# PDM-S01-V00-Microcontroller.net
KiCad netlist of a schematic drawn in Altium Designer
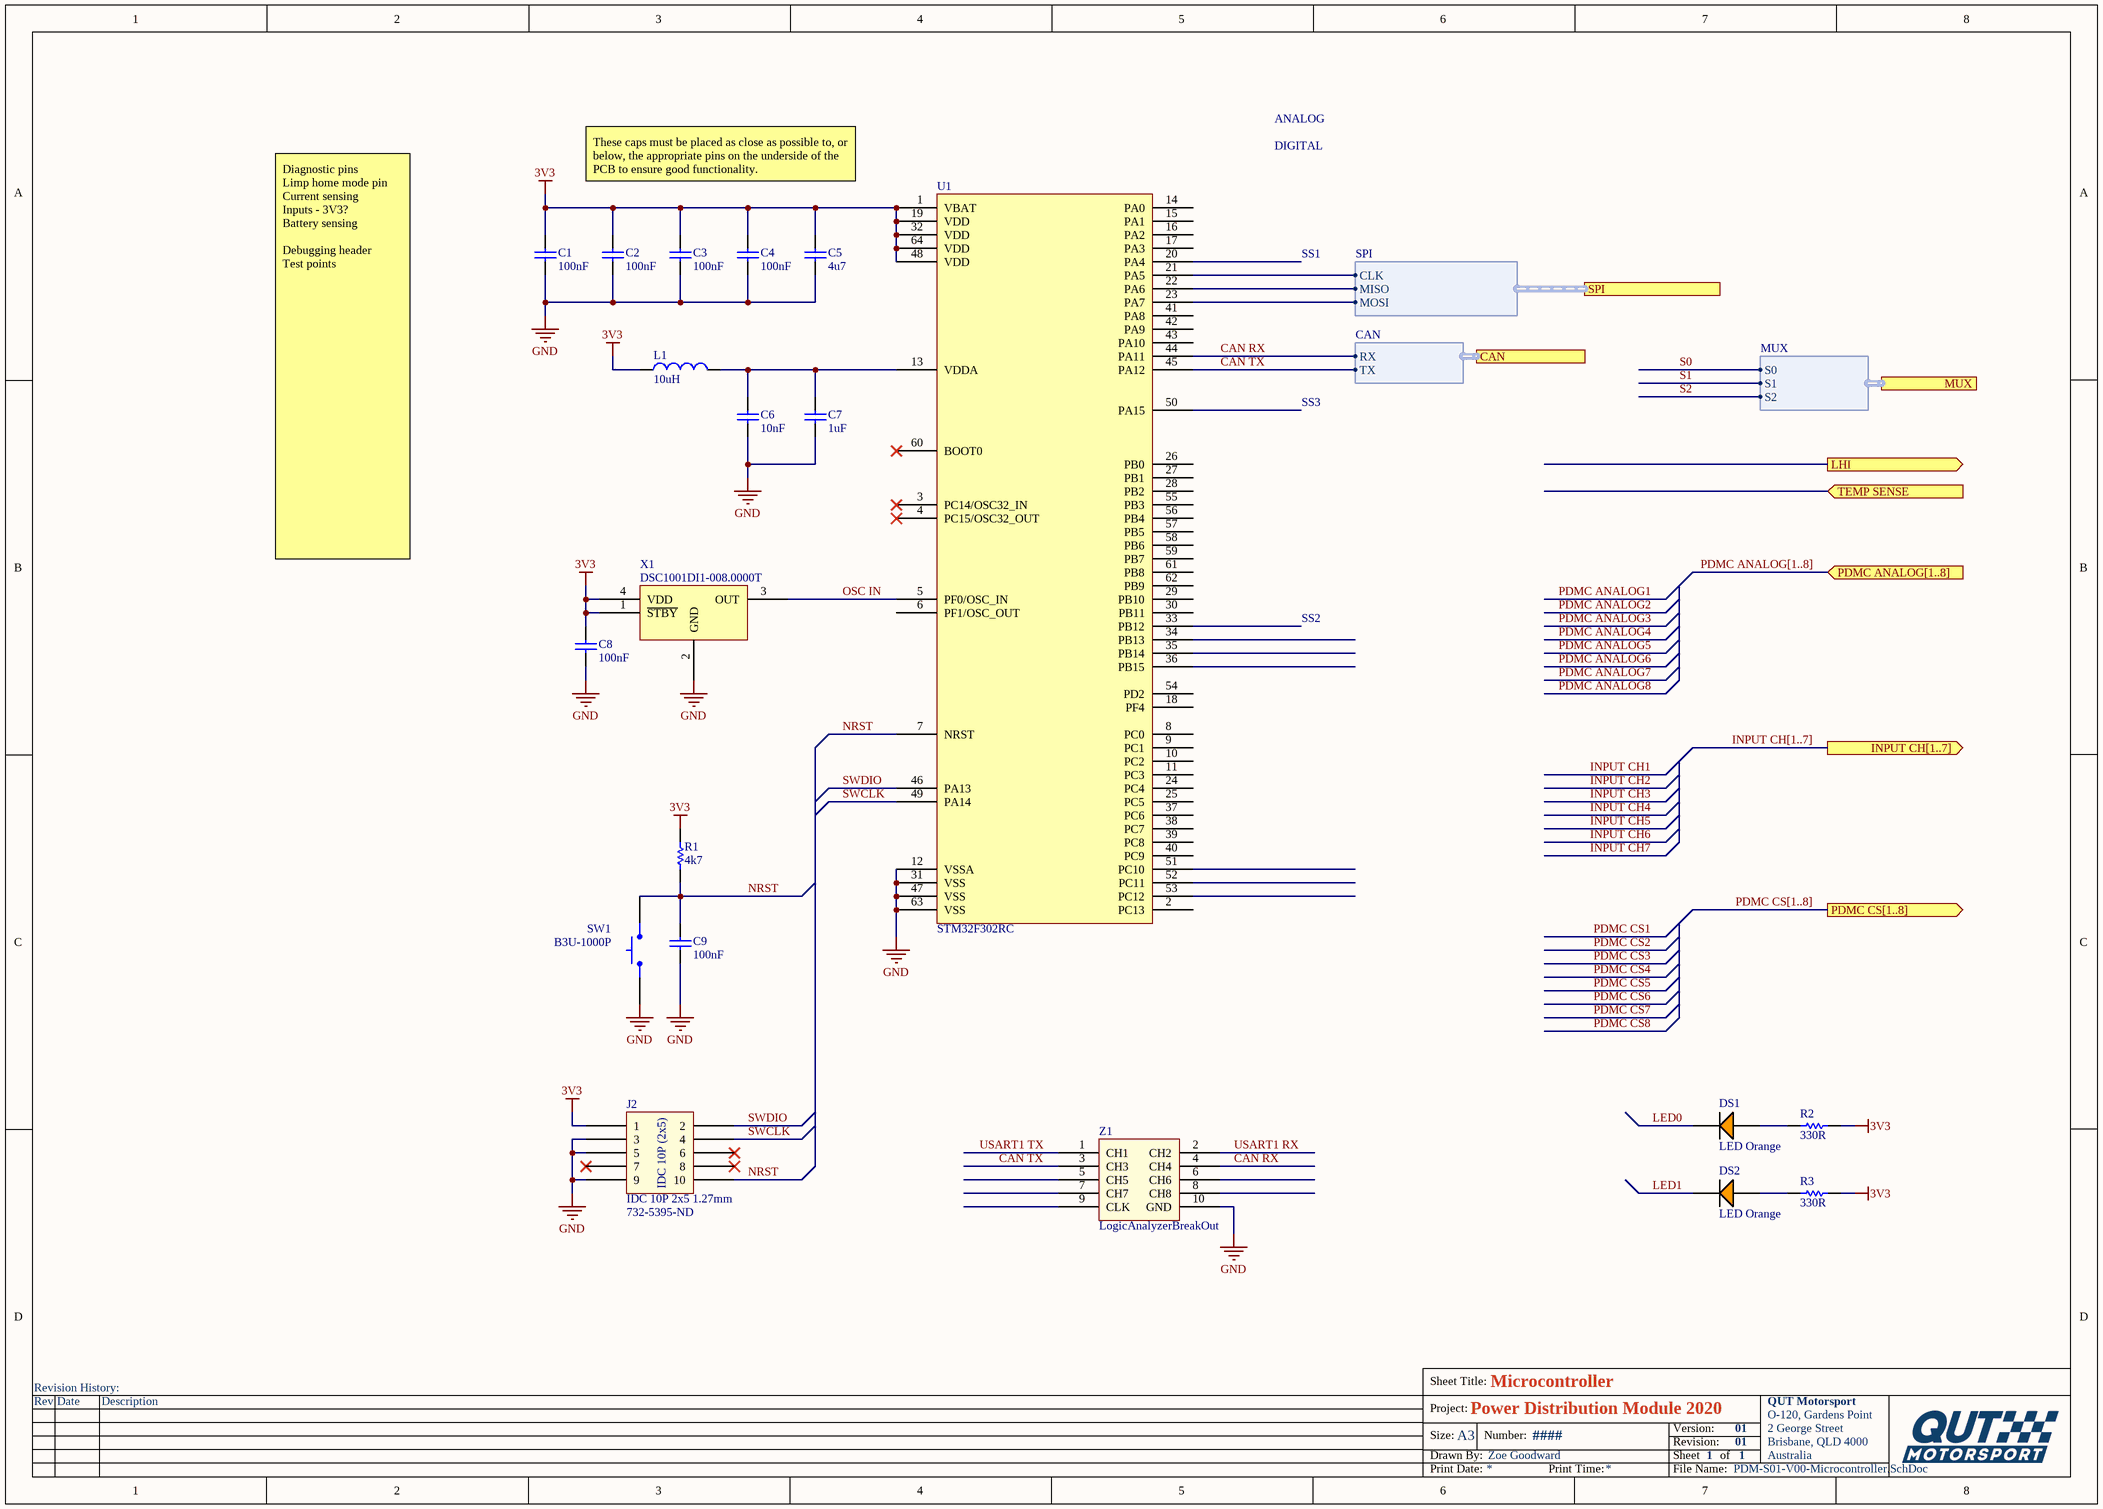
[diagram p0: PDM-S01-V00-Microcontroller.SchDoc]

(export (version "E")
  (design (tool "Eeschema 10.0.6"))
  (components
    (comp (ref "C1")
      (value "100nF")
      (footprint "Cap_Ceramic_0603")
      (description "Capacitor, Ceramic, SMD, 100nF, 50V, 5%, X7R, 0603")
      (libsource (lib "StandardCapacitors") (part "100nF 50V 5% X7R 0603"))
    )
    (comp (ref "C2")
      (value "100nF")
      (footprint "Cap_Ceramic_0603")
      (description "Capacitor, Ceramic, SMD, 100nF, 50V, 5%, X7R, 0603")
      (libsource (lib "StandardCapacitors") (part "100nF 50V 5% X7R 0603"))
    )
    (comp (ref "C3")
      (value "100nF")
      (footprint "Cap_Ceramic_0603")
      (description "Capacitor, Ceramic, SMD, 100nF, 50V, 5%, X7R, 0603")
      (libsource (lib "StandardCapacitors") (part "100nF 50V 5% X7R 0603"))
    )
    (comp (ref "C4")
      (value "100nF")
      (footprint "Cap_Ceramic_0603")
      (description "Capacitor, Ceramic, SMD, 100nF, 50V, 5%, X7R, 0603")
      (libsource (lib "StandardCapacitors") (part "100nF 50V 5% X7R 0603"))
    )
    (comp (ref "C5")
      (value "4u7")
      (footprint "Cap_Ceramic_0603")
      (description "Capacitor, Ceramic, SMD, 4u7, 50V, 5%, X7R, 0603")
      (libsource (lib "StandardCapacitors") (part "4u7 50V 5% X7R 0603"))
    )
    (comp (ref "C6")
      (value "10nF")
      (footprint "Cap_Ceramic_0603")
      (description "Capacitor, Ceramic, SMD, 10nF, 50V, 5%, X7R, 0603")
      (libsource (lib "StandardCapacitors") (part "10nF 50V 5% X7R 0603"))
    )
    (comp (ref "C7")
      (value "1uF")
      (footprint "Cap_Ceramic_0603")
      (description "Capacitor, Ceramic, SMD, 1uF, 25V, 5%, X7R, 0603")
      (libsource (lib "StandardCapacitors") (part "1uF 25V 5% X7R 0603"))
    )
    (comp (ref "C8")
      (value "100nF")
      (footprint "Cap_Ceramic_0603")
      (description "Capacitor, Ceramic, SMD, 100nF, 50V, 5%, X7R, 0603")
      (libsource (lib "StandardCapacitors") (part "100nF 50V 5% X7R 0603"))
    )
    (comp (ref "C9")
      (value "100nF")
      (footprint "Cap_Ceramic_0603")
      (description "Capacitor, Ceramic, SMD, 100nF, 50V, 5%, X7R, 0603")
      (libsource (lib "StandardCapacitors") (part "100nF 50V 5% X7R 0603"))
    )
    (comp (ref "DS1")
      (value "LED Orange")
      (footprint "LED ORANGE 0603")
      (libsource (lib "QUTMS_LEDLibrary") (part "LED ORANGE 0603"))
    )
    (comp (ref "DS2")
      (value "LED Orange")
      (footprint "LED ORANGE 0603")
      (libsource (lib "QUTMS_LEDLibrary") (part "LED ORANGE 0603"))
    )
    (comp (ref "J2")
      (value "IDC 10P 2x5 1.27mm")
      (footprint "IDC 1.27MM 10P")
      (libsource (lib "IDCConnectors") (part "IDC 10P 2x5 1.27mm"))
    )
    (comp (ref "L1")
      (value "10uH")
      (footprint "TDK-B82422A1103K100_V")
      (description "Wirewound Inductor, 10 uF, +/- 10%, 180 mA, -55 to 125 degC, 2-Pin SMD, RoHS, Tape and Reel")
      (fields (field (name "TOLERANCE") "±10%") (field (name "MANUFACTURER") "EPCOS-(TDK)"))
      (libsource (lib "Altium Content Vault") (part "IND-2"))
    )
    (comp (ref "R1")
      (value "4k7")
      (footprint "Res_ThinFilm_0603")
      (description "Resistor, SMD, 4k7, 0.1W, 5%, 0603")
      (libsource (lib "StandardResistors") (part "4k7 5% 0603"))
    )
    (comp (ref "R2")
      (value "330R")
      (footprint "Res_ThinFilm_0603")
      (description "Resistor, SMD, 330R, 0.1W, 5%, 0603")
      (libsource (lib "StandardResistors") (part "330R 5% 0603"))
    )
    (comp (ref "R3")
      (value "330R")
      (footprint "Res_ThinFilm_0603")
      (description "Resistor, SMD, 330R, 0.1W, 5%, 0603")
      (libsource (lib "StandardResistors") (part "330R 5% 0603"))
    )
    (comp (ref "SW1")
      (value "B3U-1000P")
      (footprint "BTN B3U-1000P")
      (description "Omron B3U-1000P Ultra Miniture Switch")
      (libsource (lib "QUTMS_SwitchLibrary") (part "BTN B3U-1000P"))
    )
    (comp (ref "U1")
      (value "STM32F302RC")
      (footprint "STM32F302RC")
      (description "ARM® Cortex®-M4 STM32F3 Microcontroller IC 32-Bit 72MHz 256KB (256K x 8) FLASH 64-LQFP (10x10)")
      (libsource (lib "QUTMS_STM32Library") (part "STM32F302RC"))
    )
    (comp (ref "X1")
      (value "DSC1001DI1-008.0000T")
      (footprint "DSC1001DI1-008.0000TCT-ND")
      (description "8MHz XO (Standard) CMOS Oscillator 1.8 ~ 3.3V Standby (Power Down) 4-SMD, No Lead")
      (libsource (lib "QUTMS_CrystalLibrary") (part "DSC1001DI1-008.0000T"))
    )
    (comp (ref "Z1")
      (value "LogicAnalyzerBreakOut")
      (footprint "LogicAnalyzer")
      (libsource (lib "StandardTest") (part "LogicAnalyer"))
    )
  )
  (nets
    (net (code "4") (name "/CAN RX") (class "Default")
      (node (ref "U1") (pin "44") (pinfunction "PA11_44") (pintype "passive"))
      (node (ref "Z1") (pin "4") (pinfunction "CH4_4") (pintype "passive"))
    )
    (net (code "5") (name "/CAN TX") (class "Default")
      (node (ref "U1") (pin "45") (pinfunction "PA12_45") (pintype "passive"))
      (node (ref "Z1") (pin "3") (pinfunction "CH3_3") (pintype "passive"))
    )
    (net (code "6") (name "/CLK") (class "Default")
      (node (ref "U1") (pin "21") (pinfunction "PA5_21") (pintype "passive"))
    )
    (net (code "14") (name "/LED0") (class "Default")
      (node (ref "DS1") (pin "2") (pinfunction "C_2") (pintype "passive"))
    )
    (net (code "15") (name "/LED1") (class "Default")
      (node (ref "DS2") (pin "2") (pinfunction "C_2") (pintype "passive"))
    )
    (net (code "17") (name "/MISO") (class "Default")
      (node (ref "U1") (pin "22") (pinfunction "PA6_22") (pintype "passive"))
    )
    (net (code "18") (name "/MOSI") (class "Default")
      (node (ref "U1") (pin "23") (pinfunction "PA7_23") (pintype "passive"))
    )
    (net (code "19") (name "/NRST") (class "Default")
      (node (ref "C9") (pin "2") (pinfunction "2_2") (pintype "passive"))
      (node (ref "J2") (pin "10") (pinfunction "10_10") (pintype "passive"))
      (node (ref "R1") (pin "1") (pinfunction "1_1") (pintype "passive"))
      (node (ref "SW1") (pin "2") (pinfunction "2_2") (pintype "passive"))
      (node (ref "U1") (pin "7") (pinfunction "NRST_7") (pintype "passive"))
    )
    (net (code "20") (name "/OSC IN") (class "Default")
      (node (ref "U1") (pin "5") (pinfunction "PF0/OSC_IN_5") (pintype "passive"))
      (node (ref "X1") (pin "3") (pinfunction "OUT_3") (pintype "passive"))
    )
    (net (code "40") (name "/SWCLK") (class "Default")
      (node (ref "J2") (pin "4") (pinfunction "4_4") (pintype "passive"))
      (node (ref "U1") (pin "49") (pinfunction "PA14_49") (pintype "passive"))
    )
    (net (code "41") (name "/SWDIO") (class "Default")
      (node (ref "J2") (pin "2") (pinfunction "2_2") (pintype "passive"))
      (node (ref "U1") (pin "46") (pinfunction "PA13_46") (pintype "passive"))
    )
    (net (code "43") (name "/USART1 RX") (class "Default")
      (node (ref "Z1") (pin "2") (pinfunction "CH2_2") (pintype "passive"))
    )
    (net (code "44") (name "/USART1 TX") (class "Default")
      (node (ref "Z1") (pin "1") (pinfunction "CH1_1") (pintype "passive"))
    )
    (net (code "51") (name "3V3") (class "Default")
      (node (ref "C1") (pin "2") (pinfunction "2_2") (pintype "passive"))
      (node (ref "C2") (pin "2") (pinfunction "2_2") (pintype "passive"))
      (node (ref "C3") (pin "2") (pinfunction "2_2") (pintype "passive"))
      (node (ref "C4") (pin "2") (pinfunction "2_2") (pintype "passive"))
      (node (ref "C5") (pin "2") (pinfunction "2_2") (pintype "passive"))
      (node (ref "C8") (pin "2") (pinfunction "2_2") (pintype "passive"))
      (node (ref "J2") (pin "1") (pinfunction "1_1") (pintype "passive"))
      (node (ref "L1") (pin "1") (pinfunction "1_1") (pintype "passive"))
      (node (ref "R1") (pin "2") (pinfunction "2_2") (pintype "passive"))
      (node (ref "R2") (pin "2") (pinfunction "2_2") (pintype "passive"))
      (node (ref "R3") (pin "2") (pinfunction "2_2") (pintype "passive"))
      (node (ref "U1") (pin "1") (pinfunction "VBAT_1") (pintype "passive"))
      (node (ref "U1") (pin "19") (pinfunction "VDD_19") (pintype "passive"))
      (node (ref "U1") (pin "32") (pinfunction "VDD_32") (pintype "passive"))
      (node (ref "U1") (pin "48") (pinfunction "VDD_48") (pintype "passive"))
      (node (ref "U1") (pin "64") (pinfunction "VDD_64") (pintype "passive"))
      (node (ref "X1") (pin "1") (pinfunction "~{STBY}_1") (pintype "passive"))
      (node (ref "X1") (pin "4") (pinfunction "VDD_4") (pintype "passive"))
    )
    (net (code "52") (name "GND") (class "Default")
      (node (ref "C1") (pin "1") (pinfunction "1_1") (pintype "passive"))
      (node (ref "C2") (pin "1") (pinfunction "1_1") (pintype "passive"))
      (node (ref "C3") (pin "1") (pinfunction "1_1") (pintype "passive"))
      (node (ref "C4") (pin "1") (pinfunction "1_1") (pintype "passive"))
      (node (ref "C5") (pin "1") (pinfunction "1_1") (pintype "passive"))
      (node (ref "C6") (pin "1") (pinfunction "1_1") (pintype "passive"))
      (node (ref "C7") (pin "1") (pinfunction "1_1") (pintype "passive"))
      (node (ref "C8") (pin "1") (pinfunction "1_1") (pintype "passive"))
      (node (ref "C9") (pin "1") (pinfunction "1_1") (pintype "passive"))
      (node (ref "J2") (pin "3") (pinfunction "3_3") (pintype "passive"))
      (node (ref "J2") (pin "5") (pinfunction "5_5") (pintype "passive"))
      (node (ref "J2") (pin "9") (pinfunction "9_9") (pintype "passive"))
      (node (ref "SW1") (pin "1") (pinfunction "1_1") (pintype "passive"))
      (node (ref "U1") (pin "12") (pinfunction "VSSA_12") (pintype "passive"))
      (node (ref "U1") (pin "31") (pinfunction "VSS_31") (pintype "passive"))
      (node (ref "U1") (pin "47") (pinfunction "VSS_47") (pintype "passive"))
      (node (ref "U1") (pin "63") (pinfunction "VSS_63") (pintype "passive"))
      (node (ref "X1") (pin "2") (pinfunction "GND_2") (pintype "passive"))
      (node (ref "Z1") (pin "10") (pinfunction "GND_10") (pintype "passive"))
    )
    (net (code "53") (name "Net-(DS1-A)") (class "Default")
      (node (ref "DS1") (pin "1") (pinfunction "A_1") (pintype "passive"))
      (node (ref "R2") (pin "1") (pinfunction "1_1") (pintype "passive"))
    )
    (net (code "54") (name "Net-(DS2-A)") (class "Default")
      (node (ref "DS2") (pin "1") (pinfunction "A_1") (pintype "passive"))
      (node (ref "R3") (pin "1") (pinfunction "1_1") (pintype "passive"))
    )
    (net (code "55") (name "Net-(U1-VDDA)") (class "Default")
      (node (ref "C6") (pin "2") (pinfunction "2_2") (pintype "passive"))
      (node (ref "C7") (pin "2") (pinfunction "2_2") (pintype "passive"))
      (node (ref "L1") (pin "2") (pinfunction "2_2") (pintype "passive"))
      (node (ref "U1") (pin "13") (pinfunction "VDDA_13") (pintype "passive"))
    )
    (net (code "56") (name "unconnected-(J2-Pad6)") (class "Default")
      (node (ref "J2") (pin "6") (pinfunction "6_6") (pintype "passive+no_connect"))
    )
    (net (code "57") (name "unconnected-(J2-Pad7)") (class "Default")
      (node (ref "J2") (pin "7") (pinfunction "7_7") (pintype "passive+no_connect"))
    )
    (net (code "58") (name "unconnected-(J2-Pad8)") (class "Default")
      (node (ref "J2") (pin "8") (pinfunction "8_8") (pintype "passive+no_connect"))
    )
    (net (code "59") (name "unconnected-(U1-BOOT0-Pad60)") (class "Default")
      (node (ref "U1") (pin "60") (pinfunction "BOOT0_60") (pintype "passive+no_connect"))
    )
    (net (code "60") (name "unconnected-(U1-PA0-Pad14)") (class "Default")
      (node (ref "U1") (pin "14") (pinfunction "PA0_14") (pintype "passive"))
    )
    (net (code "61") (name "unconnected-(U1-PA1-Pad15)") (class "Default")
      (node (ref "U1") (pin "15") (pinfunction "PA1_15") (pintype "passive"))
    )
    (net (code "62") (name "unconnected-(U1-PA2-Pad16)") (class "Default")
      (node (ref "U1") (pin "16") (pinfunction "PA2_16") (pintype "passive"))
    )
    (net (code "63") (name "unconnected-(U1-PA3-Pad17)") (class "Default")
      (node (ref "U1") (pin "17") (pinfunction "PA3_17") (pintype "passive"))
    )
    (net (code "64") (name "unconnected-(U1-PA4-Pad20)") (class "Default")
      (node (ref "U1") (pin "20") (pinfunction "PA4_20") (pintype "passive"))
    )
    (net (code "65") (name "unconnected-(U1-PA8-Pad41)") (class "Default")
      (node (ref "U1") (pin "41") (pinfunction "PA8_41") (pintype "passive"))
    )
    (net (code "66") (name "unconnected-(U1-PA9-Pad42)") (class "Default")
      (node (ref "U1") (pin "42") (pinfunction "PA9_42") (pintype "passive"))
    )
    (net (code "67") (name "unconnected-(U1-PA10-Pad43)") (class "Default")
      (node (ref "U1") (pin "43") (pinfunction "PA10_43") (pintype "passive"))
    )
    (net (code "68") (name "unconnected-(U1-PA15-Pad50)") (class "Default")
      (node (ref "U1") (pin "50") (pinfunction "PA15_50") (pintype "passive"))
    )
    (net (code "69") (name "unconnected-(U1-PB0-Pad26)") (class "Default")
      (node (ref "U1") (pin "26") (pinfunction "PB0_26") (pintype "passive"))
    )
    (net (code "70") (name "unconnected-(U1-PB1-Pad27)") (class "Default")
      (node (ref "U1") (pin "27") (pinfunction "PB1_27") (pintype "passive"))
    )
    (net (code "71") (name "unconnected-(U1-PB2-Pad28)") (class "Default")
      (node (ref "U1") (pin "28") (pinfunction "PB2_28") (pintype "passive"))
    )
    (net (code "72") (name "unconnected-(U1-PB3-Pad55)") (class "Default")
      (node (ref "U1") (pin "55") (pinfunction "PB3_55") (pintype "passive"))
    )
    (net (code "73") (name "unconnected-(U1-PB4-Pad56)") (class "Default")
      (node (ref "U1") (pin "56") (pinfunction "PB4_56") (pintype "passive"))
    )
    (net (code "74") (name "unconnected-(U1-PB5-Pad57)") (class "Default")
      (node (ref "U1") (pin "57") (pinfunction "PB5_57") (pintype "passive"))
    )
    (net (code "75") (name "unconnected-(U1-PB6-Pad58)") (class "Default")
      (node (ref "U1") (pin "58") (pinfunction "PB6_58") (pintype "passive"))
    )
    (net (code "76") (name "unconnected-(U1-PB7-Pad59)") (class "Default")
      (node (ref "U1") (pin "59") (pinfunction "PB7_59") (pintype "passive"))
    )
    (net (code "77") (name "unconnected-(U1-PB8-Pad61)") (class "Default")
      (node (ref "U1") (pin "61") (pinfunction "PB8_61") (pintype "passive"))
    )
    (net (code "78") (name "unconnected-(U1-PB9-Pad62)") (class "Default")
      (node (ref "U1") (pin "62") (pinfunction "PB9_62") (pintype "passive"))
    )
    (net (code "79") (name "unconnected-(U1-PB10-Pad29)") (class "Default")
      (node (ref "U1") (pin "29") (pinfunction "PB10_29") (pintype "passive"))
    )
    (net (code "80") (name "unconnected-(U1-PB11-Pad30)") (class "Default")
      (node (ref "U1") (pin "30") (pinfunction "PB11_30") (pintype "passive"))
    )
    (net (code "81") (name "unconnected-(U1-PB12-Pad33)") (class "Default")
      (node (ref "U1") (pin "33") (pinfunction "PB12_33") (pintype "passive"))
    )
    (net (code "82") (name "unconnected-(U1-PB13-Pad34)") (class "Default")
      (node (ref "U1") (pin "34") (pinfunction "PB13_34") (pintype "passive"))
    )
    (net (code "83") (name "unconnected-(U1-PB14-Pad35)") (class "Default")
      (node (ref "U1") (pin "35") (pinfunction "PB14_35") (pintype "passive"))
    )
    (net (code "84") (name "unconnected-(U1-PB15-Pad36)") (class "Default")
      (node (ref "U1") (pin "36") (pinfunction "PB15_36") (pintype "passive"))
    )
    (net (code "85") (name "unconnected-(U1-PC0-Pad8)") (class "Default")
      (node (ref "U1") (pin "8") (pinfunction "PC0_8") (pintype "passive"))
    )
    (net (code "86") (name "unconnected-(U1-PC1-Pad9)") (class "Default")
      (node (ref "U1") (pin "9") (pinfunction "PC1_9") (pintype "passive"))
    )
    (net (code "87") (name "unconnected-(U1-PC2-Pad10)") (class "Default")
      (node (ref "U1") (pin "10") (pinfunction "PC2_10") (pintype "passive"))
    )
    (net (code "88") (name "unconnected-(U1-PC3-Pad11)") (class "Default")
      (node (ref "U1") (pin "11") (pinfunction "PC3_11") (pintype "passive"))
    )
    (net (code "89") (name "unconnected-(U1-PC4-Pad24)") (class "Default")
      (node (ref "U1") (pin "24") (pinfunction "PC4_24") (pintype "passive"))
    )
    (net (code "90") (name "unconnected-(U1-PC5-Pad25)") (class "Default")
      (node (ref "U1") (pin "25") (pinfunction "PC5_25") (pintype "passive"))
    )
    (net (code "91") (name "unconnected-(U1-PC6-Pad37)") (class "Default")
      (node (ref "U1") (pin "37") (pinfunction "PC6_37") (pintype "passive"))
    )
    (net (code "92") (name "unconnected-(U1-PC7-Pad38)") (class "Default")
      (node (ref "U1") (pin "38") (pinfunction "PC7_38") (pintype "passive"))
    )
    (net (code "93") (name "unconnected-(U1-PC8-Pad39)") (class "Default")
      (node (ref "U1") (pin "39") (pinfunction "PC8_39") (pintype "passive"))
    )
    (net (code "94") (name "unconnected-(U1-PC9-Pad40)") (class "Default")
      (node (ref "U1") (pin "40") (pinfunction "PC9_40") (pintype "passive"))
    )
    (net (code "95") (name "unconnected-(U1-PC10-Pad51)") (class "Default")
      (node (ref "U1") (pin "51") (pinfunction "PC10_51") (pintype "passive"))
    )
    (net (code "96") (name "unconnected-(U1-PC11-Pad52)") (class "Default")
      (node (ref "U1") (pin "52") (pinfunction "PC11_52") (pintype "passive"))
    )
    (net (code "97") (name "unconnected-(U1-PC12-Pad53)") (class "Default")
      (node (ref "U1") (pin "53") (pinfunction "PC12_53") (pintype "passive"))
    )
    (net (code "98") (name "unconnected-(U1-PC13-Pad2)") (class "Default")
      (node (ref "U1") (pin "2") (pinfunction "PC13_2") (pintype "passive"))
    )
    (net (code "99") (name "unconnected-(U1-PC14{slash}OSC32_IN-Pad3)") (class "Default")
      (node (ref "U1") (pin "3") (pinfunction "PC14/OSC32_IN_3") (pintype "passive+no_connect"))
    )
    (net (code "100") (name "unconnected-(U1-PC15{slash}OSC32_OUT-Pad4)") (class "Default")
      (node (ref "U1") (pin "4") (pinfunction "PC15/OSC32_OUT_4") (pintype "passive+no_connect"))
    )
    (net (code "101") (name "unconnected-(U1-PD2-Pad54)") (class "Default")
      (node (ref "U1") (pin "54") (pinfunction "PD2_54") (pintype "passive"))
    )
    (net (code "102") (name "unconnected-(U1-PF1{slash}OSC_OUT-Pad6)") (class "Default")
      (node (ref "U1") (pin "6") (pinfunction "PF1/OSC_OUT_6") (pintype "passive"))
    )
    (net (code "103") (name "unconnected-(U1-PF4-Pad18)") (class "Default")
      (node (ref "U1") (pin "18") (pinfunction "PF4_18") (pintype "passive"))
    )
    (net (code "104") (name "unconnected-(Z1-CH5-Pad5)") (class "Default")
      (node (ref "Z1") (pin "5") (pinfunction "CH5_5") (pintype "passive"))
    )
    (net (code "105") (name "unconnected-(Z1-CH6-Pad6)") (class "Default")
      (node (ref "Z1") (pin "6") (pinfunction "CH6_6") (pintype "passive"))
    )
    (net (code "106") (name "unconnected-(Z1-CH7-Pad7)") (class "Default")
      (node (ref "Z1") (pin "7") (pinfunction "CH7_7") (pintype "passive"))
    )
    (net (code "107") (name "unconnected-(Z1-CH8-Pad8)") (class "Default")
      (node (ref "Z1") (pin "8") (pinfunction "CH8_8") (pintype "passive"))
    )
    (net (code "108") (name "unconnected-(Z1-CLK-Pad9)") (class "Default")
      (node (ref "Z1") (pin "9") (pinfunction "CLK_9") (pintype "passive"))
    )
  )
)
